# Sheet1.net
KiCad netlist of a schematic drawn in Altium Designer
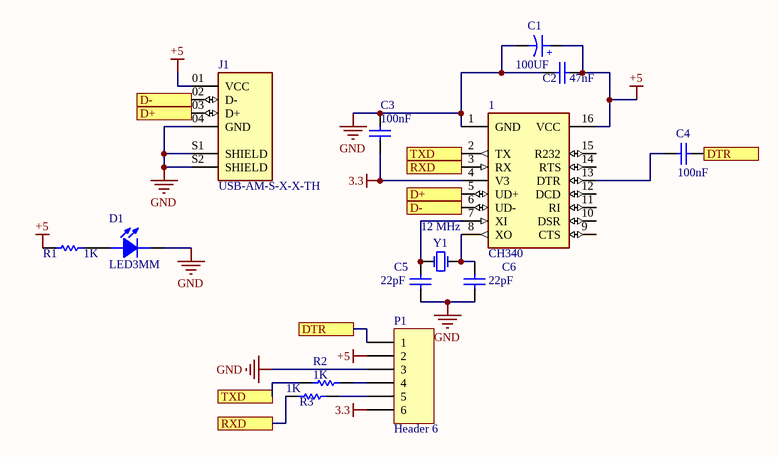
[diagram p0: Sheet1.SchDoc]

(export (version "E")
  (design (tool "Eeschema 10.0.6"))
  (components
    (comp (ref "1")
      (value "CH340")
      (footprint "SOIC16")
      (description "Circuit Breaker Magnetic 3Pole 40A 240VAC")
      (fields (field (name "MF") "Eaton"))
      (libsource (lib "CH340") (part "CH340"))
    )
    (comp (ref "C1")
      (value "100UF")
      (footprint "Cap electrolitic radial 5x12-2")
      (description "Cap electrolitic radial")
      (fields (field (name "DESIGNER") "Abbas Basereh"))
      (libsource (lib "Altium") (part "Cap ELECTROLITIC TOTAL SIZE"))
    )
    (comp (ref "C2")
      (value "47nF")
      (footprint "Cap-100nF")
      (description "CAP Ceramic Total")
      (fields (field (name "DESIGNER") "Ali Hafizi"))
      (libsource (lib "Altium") (part "CAP CERAMIC TOTAL SIZE"))
    )
    (comp (ref "C3")
      (value "100nF")
      (footprint "Cap-100nF")
      (description "CAP Ceramic Total")
      (fields (field (name "DESIGNER") "Ali Hafizi"))
      (libsource (lib "Altium") (part "CAP CERAMIC TOTAL SIZE"))
    )
    (comp (ref "C4")
      (value "100nF")
      (footprint "Cap-100nF")
      (description "CAP Ceramic Total")
      (fields (field (name "DESIGNER") "Ali Hafizi"))
      (libsource (lib "Altium") (part "CAP CERAMIC TOTAL SIZE"))
    )
    (comp (ref "C5")
      (value "22pF")
      (footprint "Cap-100nF")
      (description "CAP Ceramic Total")
      (fields (field (name "DESIGNER") "Ali Hafizi"))
      (libsource (lib "Altium") (part "CAP CERAMIC TOTAL SIZE"))
    )
    (comp (ref "C6")
      (value "22pF")
      (footprint "Cap-100nF")
      (description "CAP Ceramic Total")
      (fields (field (name "DESIGNER") "Ali Hafizi"))
      (libsource (lib "Altium") (part "CAP CERAMIC TOTAL SIZE"))
    )
    (comp (ref "D1")
      (value "LED3MM")
      (footprint "LED3mm_GRN")
      (description "Light Emitting Diode")
      (fields (field (name "DESIGNER") "Ali Hafizi"))
      (libsource (lib "Altium") (part "LED 3MM"))
    )
    (comp (ref "J1")
      (value "USB-AM-S-X-X-TH")
      (footprint "SAMTEC_USB-AM-S-X-X-TH")
      (description "USB-A (USB TYPE-A) USB 2.0 Plug Connector 4 Position Through Hole, Right Angle")
      (fields (field (name "MF") "Samtec") (field (name "MP") "USB-AM-S-F-B-TH"))
      (libsource (lib "USB-AM-S-X-X-TH") (part "USB-AM-S-X-X-TH"))
    )
    (comp (ref "P1")
      (value "Header 6")
      (footprint "HDR1X6")
      (description "Header, 6-Pin")
      (fields (field (name "PUBLISHER") "Altium Limited"))
      (libsource (lib "Altium") (part "Header 6"))
    )
    (comp (ref "R1")
      (value "1K")
      (footprint "RES-(1/4)")
      (description "TOTAL DIP RESISTOR PACK")
      (fields (field (name "DESIGNER") "Ali Hafizi"))
      (libsource (lib "Altium") (part "RES DIP PACKAGE"))
    )
    (comp (ref "R2")
      (value "1K")
      (footprint "RES-(1/4)")
      (description "TOTAL DIP RESISTOR PACK")
      (fields (field (name "DESIGNER") "Ali Hafizi"))
      (libsource (lib "Altium") (part "RES DIP PACKAGE"))
    )
    (comp (ref "R3")
      (value "1K")
      (footprint "RES-(1/4)")
      (description "TOTAL DIP RESISTOR PACK")
      (fields (field (name "DESIGNER") "Ali Hafizi"))
      (libsource (lib "Altium") (part "RES DIP PACKAGE"))
    )
    (comp (ref "Y1")
      (value "12 MHz")
      (footprint "XTAL 16MHZ")
      (description "XTAL Crystal")
      (fields (field (name "DESIGNER") "ABBAS BASEREH"))
      (libsource (lib "Altium") (part "XTAL"))
    )
  )
  (nets
    (net (code "1") (name "+5") (class "Default")
      (node (ref "1") (pin "16") (pinfunction "VCC_16") (pintype "power_in"))
      (node (ref "C1") (pin "1") (pinfunction "1_1") (pintype "passive"))
      (node (ref "C2") (pin "1") (pinfunction "1_1") (pintype "passive"))
      (node (ref "J1") (pin "01") (pinfunction "VCC_01") (pintype "power_in"))
      (node (ref "P1") (pin "2") (pinfunction "2_2") (pintype "passive"))
      (node (ref "R1") (pin "1") (pinfunction "1_1") (pintype "passive"))
    )
    (net (code "2") (name "/D+") (class "Default")
      (node (ref "1") (pin "5") (pinfunction "UD+_5") (pintype "bidirectional"))
      (node (ref "J1") (pin "03") (pinfunction "D+_03") (pintype "bidirectional"))
    )
    (net (code "3") (name "/D-") (class "Default")
      (node (ref "1") (pin "6") (pinfunction "UD-_6") (pintype "bidirectional"))
      (node (ref "J1") (pin "02") (pinfunction "D-_02") (pintype "bidirectional"))
    )
    (net (code "4") (name "/DTR") (class "Default")
      (node (ref "C4") (pin "1") (pinfunction "1_1") (pintype "passive"))
      (node (ref "P1") (pin "1") (pinfunction "1_1") (pintype "passive"))
    )
    (net (code "5") (name "/RXD") (class "Default")
      (node (ref "1") (pin "3") (pinfunction "RX_3") (pintype "input"))
      (node (ref "R2") (pin "1") (pinfunction "1_1") (pintype "passive"))
    )
    (net (code "6") (name "/TXD") (class "Default")
      (node (ref "1") (pin "2") (pinfunction "TX_2") (pintype "output"))
      (node (ref "R3") (pin "1") (pinfunction "1_1") (pintype "passive"))
    )
    (net (code "7") (name "3.3") (class "Default")
      (node (ref "1") (pin "4") (pinfunction "V3_4") (pintype "power_in"))
      (node (ref "C3") (pin "1") (pinfunction "1_1") (pintype "passive"))
      (node (ref "P1") (pin "6") (pinfunction "6_6") (pintype "passive"))
    )
    (net (code "8") (name "GND") (class "Default")
      (node (ref "1") (pin "1") (pinfunction "GND_1") (pintype "power_in"))
      (node (ref "C1") (pin "2") (pinfunction "2_2") (pintype "passive"))
      (node (ref "C2") (pin "2") (pinfunction "2_2") (pintype "passive"))
      (node (ref "C3") (pin "2") (pinfunction "2_2") (pintype "passive"))
      (node (ref "C5") (pin "1") (pinfunction "1_1") (pintype "passive"))
      (node (ref "C6") (pin "1") (pinfunction "1_1") (pintype "passive"))
      (node (ref "D1") (pin "2") (pinfunction "CATHODE_2") (pintype "passive"))
      (node (ref "J1") (pin "04") (pinfunction "GND_04") (pintype "power_in"))
      (node (ref "J1") (pin "S1") (pinfunction "SHIELD_S1") (pintype "passive"))
      (node (ref "J1") (pin "S2") (pinfunction "SHIELD_S2") (pintype "passive"))
      (node (ref "P1") (pin "3") (pinfunction "3_3") (pintype "passive"))
    )
    (net (code "9") (name "Net-(1-DTR)") (class "Default")
      (node (ref "1") (pin "13") (pinfunction "DTR_13") (pintype "bidirectional"))
      (node (ref "C4") (pin "2") (pinfunction "2_2") (pintype "passive"))
    )
    (net (code "10") (name "Net-(1-XI)") (class "Default")
      (node (ref "1") (pin "7") (pinfunction "XI_7") (pintype "input"))
      (node (ref "C5") (pin "2") (pinfunction "2_2") (pintype "passive"))
      (node (ref "Y1") (pin "1") (pinfunction "OSC1_1") (pintype "passive"))
    )
    (net (code "11") (name "Net-(1-XO)") (class "Default")
      (node (ref "1") (pin "8") (pinfunction "XO_8") (pintype "output"))
      (node (ref "C6") (pin "2") (pinfunction "2_2") (pintype "passive"))
      (node (ref "Y1") (pin "2") (pinfunction "OSC2_2") (pintype "passive"))
    )
    (net (code "12") (name "Net-(D1-ANODE)") (class "Default")
      (node (ref "D1") (pin "1") (pinfunction "ANODE_1") (pintype "passive"))
      (node (ref "R1") (pin "2") (pinfunction "2_2") (pintype "passive"))
    )
    (net (code "13") (name "Net-(P1-Pad4)") (class "Default")
      (node (ref "P1") (pin "4") (pinfunction "4_4") (pintype "passive"))
      (node (ref "R3") (pin "2") (pinfunction "2_2") (pintype "passive"))
    )
    (net (code "14") (name "Net-(P1-Pad5)") (class "Default")
      (node (ref "P1") (pin "5") (pinfunction "5_5") (pintype "passive"))
      (node (ref "R2") (pin "2") (pinfunction "2_2") (pintype "passive"))
    )
    (net (code "15") (name "unconnected-(1-CTS-Pad9)") (class "Default")
      (node (ref "1") (pin "9") (pinfunction "CTS_9") (pintype "bidirectional"))
    )
    (net (code "16") (name "unconnected-(1-DCD-Pad12)") (class "Default")
      (node (ref "1") (pin "12") (pinfunction "DCD_12") (pintype "bidirectional"))
    )
    (net (code "17") (name "unconnected-(1-DSR-Pad10)") (class "Default")
      (node (ref "1") (pin "10") (pinfunction "DSR_10") (pintype "bidirectional"))
    )
    (net (code "18") (name "unconnected-(1-R232-Pad15)") (class "Default")
      (node (ref "1") (pin "15") (pinfunction "R232_15") (pintype "bidirectional"))
    )
    (net (code "19") (name "unconnected-(1-RI-Pad11)") (class "Default")
      (node (ref "1") (pin "11") (pinfunction "RI_11") (pintype "bidirectional"))
    )
    (net (code "20") (name "unconnected-(1-RTS-Pad14)") (class "Default")
      (node (ref "1") (pin "14") (pinfunction "RTS_14") (pintype "bidirectional"))
    )
  )
)
